# io-bus.net
KiCad netlist of a schematic drawn in Altium Designer
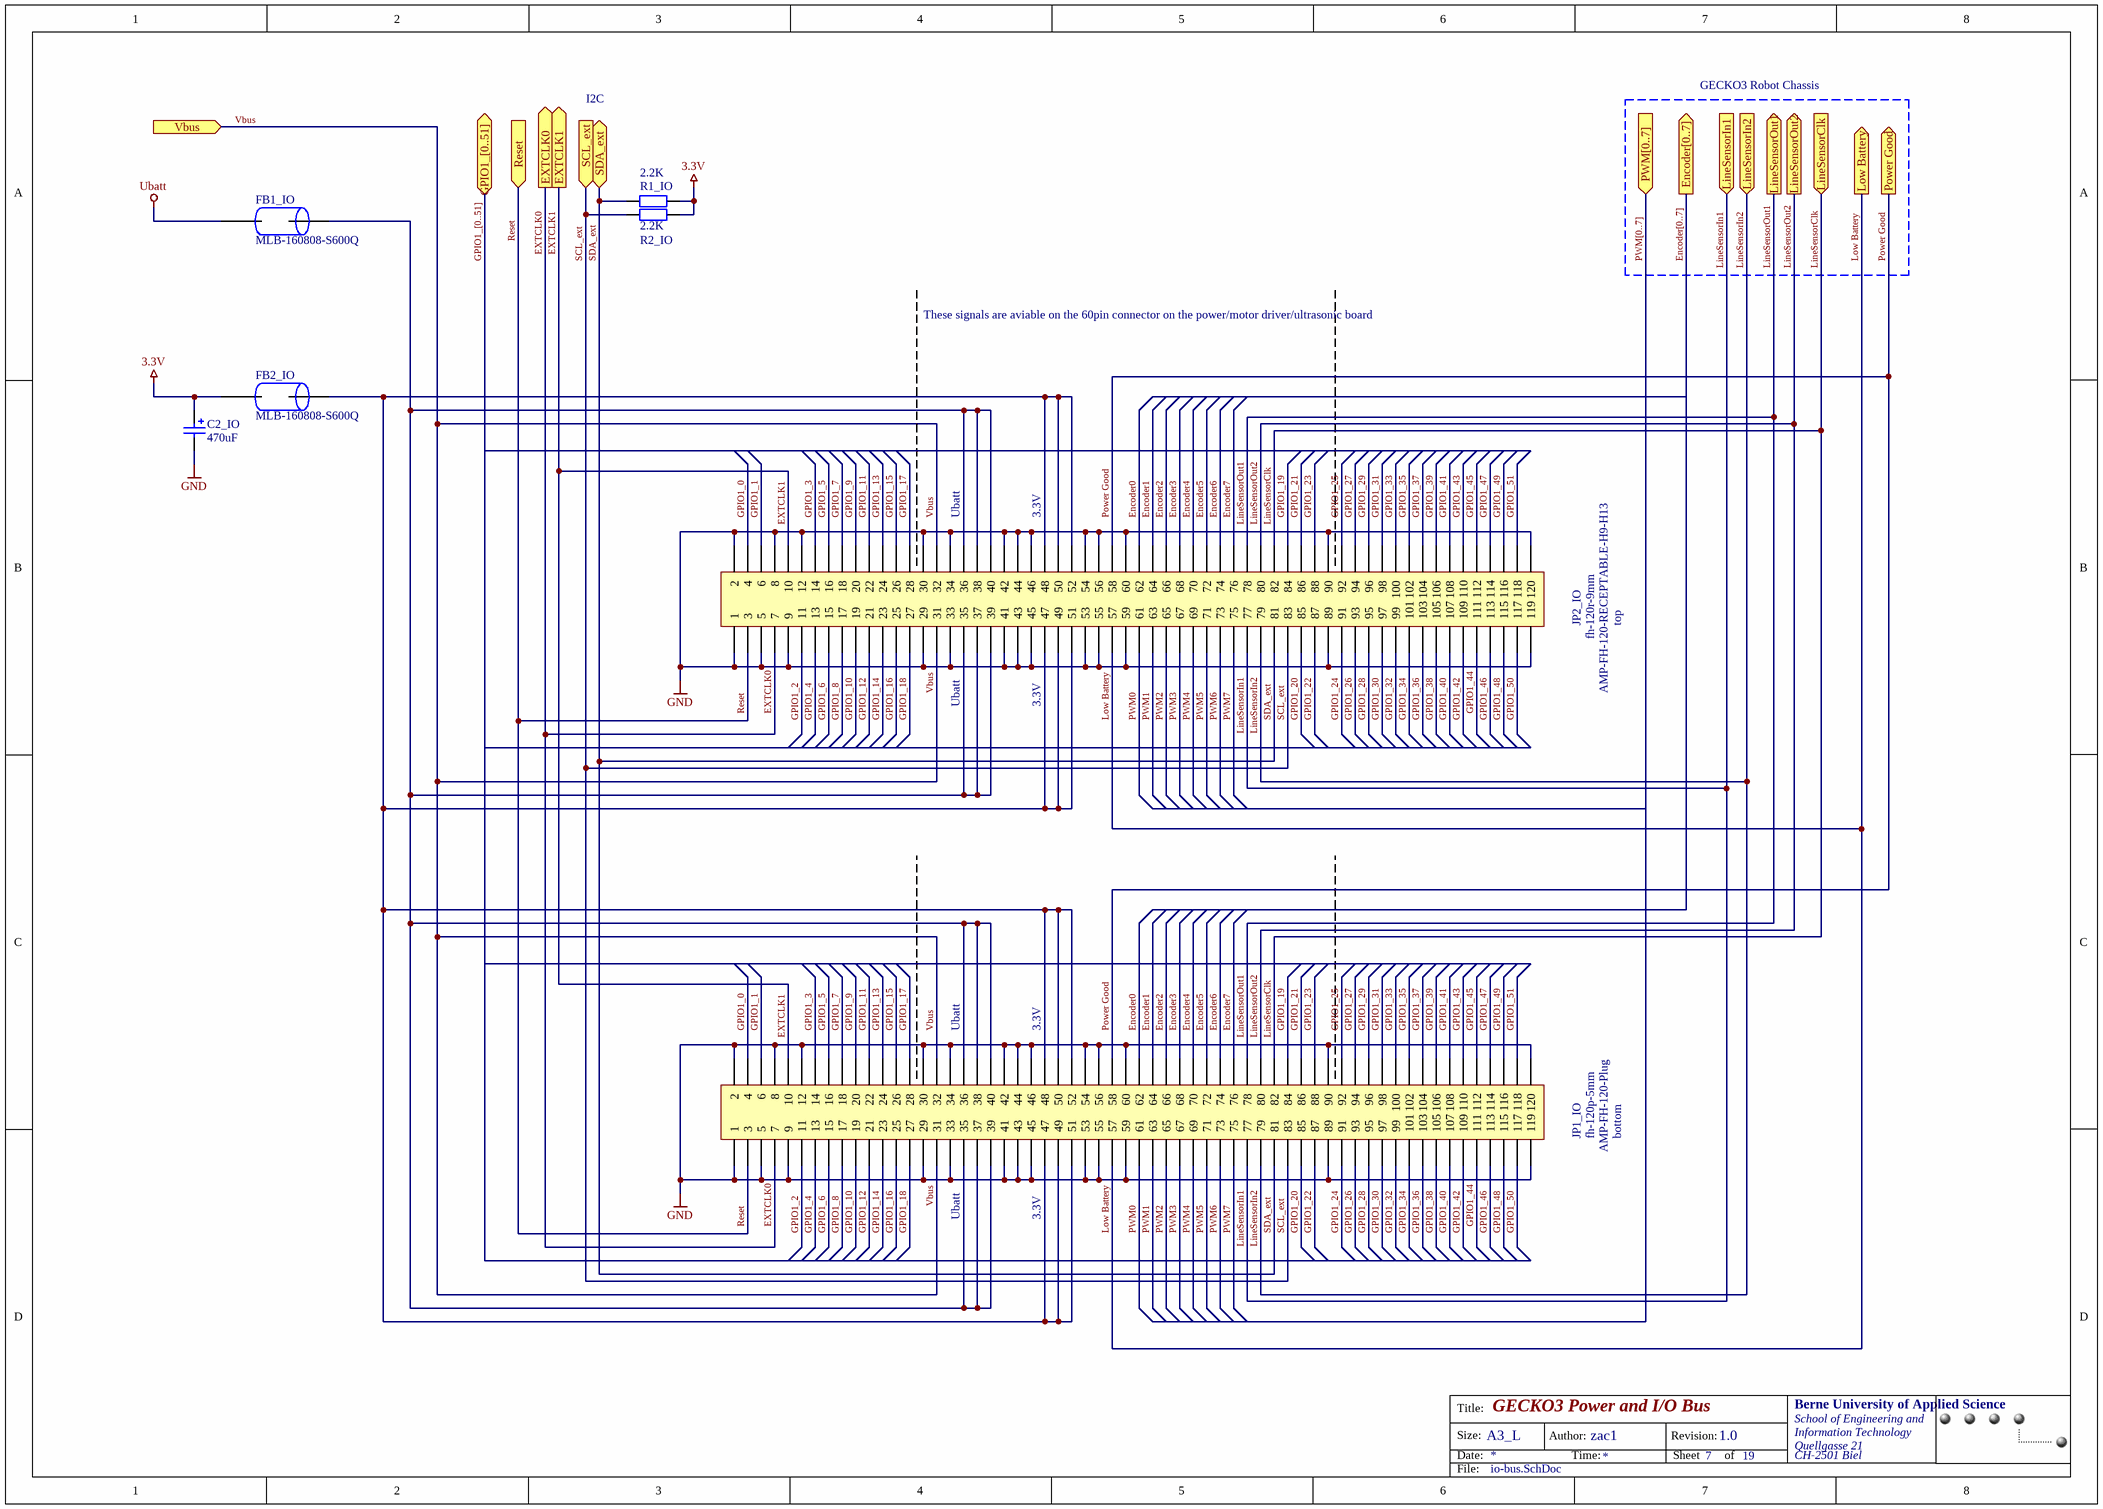
[diagram p0: io-bus.SchDoc]

(export (version "E")
  (design (tool "Eeschema 10.0.6"))
  (components
    (comp (ref "C2_IO")
      (value "470uF")
      (footprint "D")
      (description "Polarized Capacitor (Surface Mount)")
      (fields
        (field (name "MANUFACTURER") "Kemet")
        (field (name "PART NUMBER") "B45196-H2477-K509 ")
        (field (name "PUBLISHER") "Altium Limited")
      )
      (libsource (lib "Miscellaneous Devices") (part "Cap Pol3"))
    )
    (comp (ref "FB1_IO")
      (value "MLB-160808-S600Q")
      (footprint "0603")
      (fields (field (name "MANUFACTURER") "Kitagawa") (field (name "Comment") "FERRITE-BEAD"))
      (libsource (lib "gecko3-user") (part "FERRITE-BEAD"))
    )
    (comp (ref "FB2_IO")
      (value "MLB-160808-S600Q")
      (footprint "0603")
      (fields (field (name "MANUFACTURER") "Kitagawa") (field (name "Comment") "FERRITE-BEAD"))
      (libsource (lib "gecko3-user") (part "FERRITE-BEAD"))
    )
    (comp (ref "JP1_IO")
      (value "AMP-FH-120-Plug")
      (footprint "amp_FH_.8mm_120pin_plug")
      (description "AMP Free Height System, 0.8mm, 120 Pin, Plug")
      (fields
        (field (name "COMMENT_1") "bottom")
        (field (name "ALTIUM_VALUE") "fh-120p-5mm")
        (field (name "MANUFACTURER") "AMP")
        (field (name "PART NUMBER") "5177984-5")
      )
      (libsource (lib "gecko3-user") (part "AMP-FH-120-Plug"))
    )
    (comp (ref "JP2_IO")
      (value "AMP-FH-120-RECEPTABLE-H9-H13")
      (footprint "amp_FH_.8mm_120pin_r_H9_H13")
      (description "AMP Free Height System, 0.8mm, 120 Pin, 9 or 13mm Height, Receptable")
      (fields
        (field (name "ALTIUM_VALUE") "fh-120r-9mm")
        (field (name "COMMENT_1") "top")
        (field (name "MANUFACTURER") "AMP")
        (field (name "PART NUMBER") "5-5179009-5")
      )
      (libsource (lib "gecko3-user") (part "AMP-FH-120-RECEPTABLE-H9-H13"))
    )
    (comp (ref "R1_IO")
      (value "2.2K")
      (footprint "0402")
      (description "Resistor")
      (fields
        (field (name "MANUFACTURER") "PHYCOMP")
        (field (name "PART NUMBER") "232270672202")
        (field (name "PUBLISHER") "Altium Limited")
      )
      (libsource (lib "Miscellaneous Devices") (part "Res2"))
    )
    (comp (ref "R2_IO")
      (value "2.2K")
      (footprint "0402")
      (description "Resistor")
      (fields
        (field (name "MANUFACTURER") "PHYCOMP")
        (field (name "PART NUMBER") "232270672202")
        (field (name "PUBLISHER") "Altium Limited")
      )
      (libsource (lib "Miscellaneous Devices") (part "Res2"))
    )
  )
  (nets
    (net (code "1") (name "/EXTCLK0") (class "Default")
      (node (ref "JP1_IO") (pin "7") (pinfunction "7_7") (pintype "passive"))
      (node (ref "JP2_IO") (pin "7") (pinfunction "7_7") (pintype "passive"))
    )
    (net (code "2") (name "/EXTCLK1") (class "Default")
      (node (ref "JP1_IO") (pin "10") (pinfunction "10_10") (pintype "passive"))
      (node (ref "JP2_IO") (pin "10") (pinfunction "10_10") (pintype "passive"))
    )
    (net (code "3") (name "/Encoder0") (class "Default")
      (node (ref "JP1_IO") (pin "62") (pinfunction "62_62") (pintype "passive"))
      (node (ref "JP2_IO") (pin "62") (pinfunction "62_62") (pintype "passive"))
    )
    (net (code "4") (name "/Encoder1") (class "Default")
      (node (ref "JP1_IO") (pin "64") (pinfunction "64_64") (pintype "passive"))
      (node (ref "JP2_IO") (pin "64") (pinfunction "64_64") (pintype "passive"))
    )
    (net (code "5") (name "/Encoder2") (class "Default")
      (node (ref "JP1_IO") (pin "66") (pinfunction "66_66") (pintype "passive"))
      (node (ref "JP2_IO") (pin "66") (pinfunction "66_66") (pintype "passive"))
    )
    (net (code "6") (name "/Encoder3") (class "Default")
      (node (ref "JP1_IO") (pin "68") (pinfunction "68_68") (pintype "passive"))
      (node (ref "JP2_IO") (pin "68") (pinfunction "68_68") (pintype "passive"))
    )
    (net (code "7") (name "/Encoder4") (class "Default")
      (node (ref "JP1_IO") (pin "70") (pinfunction "70_70") (pintype "passive"))
      (node (ref "JP2_IO") (pin "70") (pinfunction "70_70") (pintype "passive"))
    )
    (net (code "8") (name "/Encoder5") (class "Default")
      (node (ref "JP1_IO") (pin "72") (pinfunction "72_72") (pintype "passive"))
      (node (ref "JP2_IO") (pin "72") (pinfunction "72_72") (pintype "passive"))
    )
    (net (code "9") (name "/Encoder6") (class "Default")
      (node (ref "JP1_IO") (pin "74") (pinfunction "74_74") (pintype "passive"))
      (node (ref "JP2_IO") (pin "74") (pinfunction "74_74") (pintype "passive"))
    )
    (net (code "10") (name "/Encoder7") (class "Default")
      (node (ref "JP1_IO") (pin "76") (pinfunction "76_76") (pintype "passive"))
      (node (ref "JP2_IO") (pin "76") (pinfunction "76_76") (pintype "passive"))
    )
    (net (code "12") (name "/GPIO1_0") (class "Default")
      (node (ref "JP1_IO") (pin "4") (pinfunction "4_4") (pintype "passive"))
      (node (ref "JP2_IO") (pin "4") (pinfunction "4_4") (pintype "passive"))
    )
    (net (code "13") (name "/GPIO1_1") (class "Default")
      (node (ref "JP1_IO") (pin "6") (pinfunction "6_6") (pintype "passive"))
      (node (ref "JP2_IO") (pin "6") (pinfunction "6_6") (pintype "passive"))
    )
    (net (code "14") (name "/GPIO1_2") (class "Default")
      (node (ref "JP1_IO") (pin "11") (pinfunction "11_11") (pintype "passive"))
      (node (ref "JP2_IO") (pin "11") (pinfunction "11_11") (pintype "passive"))
    )
    (net (code "15") (name "/GPIO1_3") (class "Default")
      (node (ref "JP1_IO") (pin "14") (pinfunction "14_14") (pintype "passive"))
      (node (ref "JP2_IO") (pin "14") (pinfunction "14_14") (pintype "passive"))
    )
    (net (code "16") (name "/GPIO1_4") (class "Default")
      (node (ref "JP1_IO") (pin "13") (pinfunction "13_13") (pintype "passive"))
      (node (ref "JP2_IO") (pin "13") (pinfunction "13_13") (pintype "passive"))
    )
    (net (code "17") (name "/GPIO1_5") (class "Default")
      (node (ref "JP1_IO") (pin "16") (pinfunction "16_16") (pintype "passive"))
      (node (ref "JP2_IO") (pin "16") (pinfunction "16_16") (pintype "passive"))
    )
    (net (code "18") (name "/GPIO1_6") (class "Default")
      (node (ref "JP1_IO") (pin "15") (pinfunction "15_15") (pintype "passive"))
      (node (ref "JP2_IO") (pin "15") (pinfunction "15_15") (pintype "passive"))
    )
    (net (code "19") (name "/GPIO1_7") (class "Default")
      (node (ref "JP1_IO") (pin "18") (pinfunction "18_18") (pintype "passive"))
      (node (ref "JP2_IO") (pin "18") (pinfunction "18_18") (pintype "passive"))
    )
    (net (code "20") (name "/GPIO1_8") (class "Default")
      (node (ref "JP1_IO") (pin "17") (pinfunction "17_17") (pintype "passive"))
      (node (ref "JP2_IO") (pin "17") (pinfunction "17_17") (pintype "passive"))
    )
    (net (code "21") (name "/GPIO1_9") (class "Default")
      (node (ref "JP1_IO") (pin "20") (pinfunction "20_20") (pintype "passive"))
      (node (ref "JP2_IO") (pin "20") (pinfunction "20_20") (pintype "passive"))
    )
    (net (code "22") (name "/GPIO1_10") (class "Default")
      (node (ref "JP1_IO") (pin "19") (pinfunction "19_19") (pintype "passive"))
      (node (ref "JP2_IO") (pin "19") (pinfunction "19_19") (pintype "passive"))
    )
    (net (code "23") (name "/GPIO1_11") (class "Default")
      (node (ref "JP1_IO") (pin "22") (pinfunction "22_22") (pintype "passive"))
      (node (ref "JP2_IO") (pin "22") (pinfunction "22_22") (pintype "passive"))
    )
    (net (code "24") (name "/GPIO1_12") (class "Default")
      (node (ref "JP1_IO") (pin "21") (pinfunction "21_21") (pintype "passive"))
      (node (ref "JP2_IO") (pin "21") (pinfunction "21_21") (pintype "passive"))
    )
    (net (code "25") (name "/GPIO1_13") (class "Default")
      (node (ref "JP1_IO") (pin "24") (pinfunction "24_24") (pintype "passive"))
      (node (ref "JP2_IO") (pin "24") (pinfunction "24_24") (pintype "passive"))
    )
    (net (code "26") (name "/GPIO1_14") (class "Default")
      (node (ref "JP1_IO") (pin "23") (pinfunction "23_23") (pintype "passive"))
      (node (ref "JP2_IO") (pin "23") (pinfunction "23_23") (pintype "passive"))
    )
    (net (code "27") (name "/GPIO1_15") (class "Default")
      (node (ref "JP1_IO") (pin "26") (pinfunction "26_26") (pintype "passive"))
      (node (ref "JP2_IO") (pin "26") (pinfunction "26_26") (pintype "passive"))
    )
    (net (code "28") (name "/GPIO1_16") (class "Default")
      (node (ref "JP1_IO") (pin "25") (pinfunction "25_25") (pintype "passive"))
      (node (ref "JP2_IO") (pin "25") (pinfunction "25_25") (pintype "passive"))
    )
    (net (code "29") (name "/GPIO1_17") (class "Default")
      (node (ref "JP1_IO") (pin "28") (pinfunction "28_28") (pintype "passive"))
      (node (ref "JP2_IO") (pin "28") (pinfunction "28_28") (pintype "passive"))
    )
    (net (code "30") (name "/GPIO1_18") (class "Default")
      (node (ref "JP1_IO") (pin "27") (pinfunction "27_27") (pintype "passive"))
      (node (ref "JP2_IO") (pin "27") (pinfunction "27_27") (pintype "passive"))
    )
    (net (code "31") (name "/GPIO1_19") (class "Default")
      (node (ref "JP1_IO") (pin "84") (pinfunction "84_84") (pintype "passive"))
      (node (ref "JP2_IO") (pin "84") (pinfunction "84_84") (pintype "passive"))
    )
    (net (code "32") (name "/GPIO1_20") (class "Default")
      (node (ref "JP1_IO") (pin "85") (pinfunction "85_85") (pintype "passive"))
      (node (ref "JP2_IO") (pin "85") (pinfunction "85_85") (pintype "passive"))
    )
    (net (code "33") (name "/GPIO1_21") (class "Default")
      (node (ref "JP1_IO") (pin "86") (pinfunction "86_86") (pintype "passive"))
      (node (ref "JP2_IO") (pin "86") (pinfunction "86_86") (pintype "passive"))
    )
    (net (code "34") (name "/GPIO1_22") (class "Default")
      (node (ref "JP1_IO") (pin "87") (pinfunction "87_87") (pintype "passive"))
      (node (ref "JP2_IO") (pin "87") (pinfunction "87_87") (pintype "passive"))
    )
    (net (code "35") (name "/GPIO1_23") (class "Default")
      (node (ref "JP1_IO") (pin "88") (pinfunction "88_88") (pintype "passive"))
      (node (ref "JP2_IO") (pin "88") (pinfunction "88_88") (pintype "passive"))
    )
    (net (code "36") (name "/GPIO1_24") (class "Default")
      (node (ref "JP1_IO") (pin "91") (pinfunction "91_91") (pintype "passive"))
      (node (ref "JP2_IO") (pin "91") (pinfunction "91_91") (pintype "passive"))
    )
    (net (code "37") (name "/GPIO1_25") (class "Default")
      (node (ref "JP1_IO") (pin "92") (pinfunction "92_92") (pintype "passive"))
      (node (ref "JP2_IO") (pin "92") (pinfunction "92_92") (pintype "passive"))
    )
    (net (code "38") (name "/GPIO1_26") (class "Default")
      (node (ref "JP1_IO") (pin "93") (pinfunction "93_93") (pintype "passive"))
      (node (ref "JP2_IO") (pin "93") (pinfunction "93_93") (pintype "passive"))
    )
    (net (code "39") (name "/GPIO1_27") (class "Default")
      (node (ref "JP1_IO") (pin "94") (pinfunction "94_94") (pintype "passive"))
      (node (ref "JP2_IO") (pin "94") (pinfunction "94_94") (pintype "passive"))
    )
    (net (code "40") (name "/GPIO1_28") (class "Default")
      (node (ref "JP1_IO") (pin "95") (pinfunction "95_95") (pintype "passive"))
      (node (ref "JP2_IO") (pin "95") (pinfunction "95_95") (pintype "passive"))
    )
    (net (code "41") (name "/GPIO1_29") (class "Default")
      (node (ref "JP1_IO") (pin "96") (pinfunction "96_96") (pintype "passive"))
      (node (ref "JP2_IO") (pin "96") (pinfunction "96_96") (pintype "passive"))
    )
    (net (code "42") (name "/GPIO1_30") (class "Default")
      (node (ref "JP1_IO") (pin "97") (pinfunction "97_97") (pintype "passive"))
      (node (ref "JP2_IO") (pin "97") (pinfunction "97_97") (pintype "passive"))
    )
    (net (code "43") (name "/GPIO1_31") (class "Default")
      (node (ref "JP1_IO") (pin "98") (pinfunction "98_98") (pintype "passive"))
      (node (ref "JP2_IO") (pin "98") (pinfunction "98_98") (pintype "passive"))
    )
    (net (code "44") (name "/GPIO1_32") (class "Default")
      (node (ref "JP1_IO") (pin "99") (pinfunction "99_99") (pintype "passive"))
      (node (ref "JP2_IO") (pin "99") (pinfunction "99_99") (pintype "passive"))
    )
    (net (code "45") (name "/GPIO1_33") (class "Default")
      (node (ref "JP1_IO") (pin "100") (pinfunction "100_100") (pintype "passive"))
      (node (ref "JP2_IO") (pin "100") (pinfunction "100_100") (pintype "passive"))
    )
    (net (code "46") (name "/GPIO1_34") (class "Default")
      (node (ref "JP1_IO") (pin "101") (pinfunction "101_101") (pintype "passive"))
      (node (ref "JP2_IO") (pin "101") (pinfunction "101_101") (pintype "passive"))
    )
    (net (code "47") (name "/GPIO1_35") (class "Default")
      (node (ref "JP1_IO") (pin "102") (pinfunction "102_102") (pintype "passive"))
      (node (ref "JP2_IO") (pin "102") (pinfunction "102_102") (pintype "passive"))
    )
    (net (code "48") (name "/GPIO1_36") (class "Default")
      (node (ref "JP1_IO") (pin "103") (pinfunction "103_103") (pintype "passive"))
      (node (ref "JP2_IO") (pin "103") (pinfunction "103_103") (pintype "passive"))
    )
    (net (code "49") (name "/GPIO1_37") (class "Default")
      (node (ref "JP1_IO") (pin "104") (pinfunction "104_104") (pintype "passive"))
      (node (ref "JP2_IO") (pin "104") (pinfunction "104_104") (pintype "passive"))
    )
    (net (code "50") (name "/GPIO1_38") (class "Default")
      (node (ref "JP1_IO") (pin "105") (pinfunction "105_105") (pintype "passive"))
      (node (ref "JP2_IO") (pin "105") (pinfunction "105_105") (pintype "passive"))
    )
    (net (code "51") (name "/GPIO1_39") (class "Default")
      (node (ref "JP1_IO") (pin "106") (pinfunction "106_106") (pintype "passive"))
      (node (ref "JP2_IO") (pin "106") (pinfunction "106_106") (pintype "passive"))
    )
    (net (code "52") (name "/GPIO1_40") (class "Default")
      (node (ref "JP1_IO") (pin "107") (pinfunction "107_107") (pintype "passive"))
      (node (ref "JP2_IO") (pin "107") (pinfunction "107_107") (pintype "passive"))
    )
    (net (code "53") (name "/GPIO1_41") (class "Default")
      (node (ref "JP1_IO") (pin "108") (pinfunction "108_108") (pintype "passive"))
      (node (ref "JP2_IO") (pin "108") (pinfunction "108_108") (pintype "passive"))
    )
    (net (code "54") (name "/GPIO1_42") (class "Default")
      (node (ref "JP1_IO") (pin "109") (pinfunction "109_109") (pintype "passive"))
      (node (ref "JP2_IO") (pin "109") (pinfunction "109_109") (pintype "passive"))
    )
    (net (code "55") (name "/GPIO1_43") (class "Default")
      (node (ref "JP1_IO") (pin "110") (pinfunction "110_110") (pintype "passive"))
      (node (ref "JP2_IO") (pin "110") (pinfunction "110_110") (pintype "passive"))
    )
    (net (code "56") (name "/GPIO1_44") (class "Default")
      (node (ref "JP1_IO") (pin "111") (pinfunction "111_111") (pintype "passive"))
      (node (ref "JP2_IO") (pin "111") (pinfunction "111_111") (pintype "passive"))
    )
    (net (code "57") (name "/GPIO1_45") (class "Default")
      (node (ref "JP1_IO") (pin "112") (pinfunction "112_112") (pintype "passive"))
      (node (ref "JP2_IO") (pin "112") (pinfunction "112_112") (pintype "passive"))
    )
    (net (code "58") (name "/GPIO1_46") (class "Default")
      (node (ref "JP1_IO") (pin "113") (pinfunction "113_113") (pintype "passive"))
      (node (ref "JP2_IO") (pin "113") (pinfunction "113_113") (pintype "passive"))
    )
    (net (code "59") (name "/GPIO1_47") (class "Default")
      (node (ref "JP1_IO") (pin "114") (pinfunction "114_114") (pintype "passive"))
      (node (ref "JP2_IO") (pin "114") (pinfunction "114_114") (pintype "passive"))
    )
    (net (code "60") (name "/GPIO1_48") (class "Default")
      (node (ref "JP1_IO") (pin "115") (pinfunction "115_115") (pintype "passive"))
      (node (ref "JP2_IO") (pin "115") (pinfunction "115_115") (pintype "passive"))
    )
    (net (code "61") (name "/GPIO1_49") (class "Default")
      (node (ref "JP1_IO") (pin "116") (pinfunction "116_116") (pintype "passive"))
      (node (ref "JP2_IO") (pin "116") (pinfunction "116_116") (pintype "passive"))
    )
    (net (code "62") (name "/GPIO1_50") (class "Default")
      (node (ref "JP1_IO") (pin "117") (pinfunction "117_117") (pintype "passive"))
      (node (ref "JP2_IO") (pin "117") (pinfunction "117_117") (pintype "passive"))
    )
    (net (code "63") (name "/GPIO1_51") (class "Default")
      (node (ref "JP1_IO") (pin "118") (pinfunction "118_118") (pintype "passive"))
      (node (ref "JP2_IO") (pin "118") (pinfunction "118_118") (pintype "passive"))
    )
    (net (code "65") (name "/LineSensorClk") (class "Default")
      (node (ref "JP1_IO") (pin "82") (pinfunction "82_82") (pintype "passive"))
      (node (ref "JP2_IO") (pin "82") (pinfunction "82_82") (pintype "passive"))
    )
    (net (code "66") (name "/LineSensorIn1") (class "Default")
      (node (ref "JP1_IO") (pin "77") (pinfunction "77_77") (pintype "passive"))
      (node (ref "JP2_IO") (pin "77") (pinfunction "77_77") (pintype "passive"))
    )
    (net (code "67") (name "/LineSensorIn2") (class "Default")
      (node (ref "JP1_IO") (pin "79") (pinfunction "79_79") (pintype "passive"))
      (node (ref "JP2_IO") (pin "79") (pinfunction "79_79") (pintype "passive"))
    )
    (net (code "68") (name "/LineSensorOut1") (class "Default")
      (node (ref "JP1_IO") (pin "78") (pinfunction "78_78") (pintype "passive"))
      (node (ref "JP2_IO") (pin "78") (pinfunction "78_78") (pintype "passive"))
    )
    (net (code "69") (name "/LineSensorOut2") (class "Default")
      (node (ref "JP1_IO") (pin "80") (pinfunction "80_80") (pintype "passive"))
      (node (ref "JP2_IO") (pin "80") (pinfunction "80_80") (pintype "passive"))
    )
    (net (code "70") (name "/Low Battery") (class "Default")
      (node (ref "JP1_IO") (pin "57") (pinfunction "57_57") (pintype "passive"))
      (node (ref "JP2_IO") (pin "57") (pinfunction "57_57") (pintype "passive"))
    )
    (net (code "71") (name "/PWM0") (class "Default")
      (node (ref "JP1_IO") (pin "61") (pinfunction "61_61") (pintype "passive"))
      (node (ref "JP2_IO") (pin "61") (pinfunction "61_61") (pintype "passive"))
    )
    (net (code "72") (name "/PWM1") (class "Default")
      (node (ref "JP1_IO") (pin "63") (pinfunction "63_63") (pintype "passive"))
      (node (ref "JP2_IO") (pin "63") (pinfunction "63_63") (pintype "passive"))
    )
    (net (code "73") (name "/PWM2") (class "Default")
      (node (ref "JP1_IO") (pin "65") (pinfunction "65_65") (pintype "passive"))
      (node (ref "JP2_IO") (pin "65") (pinfunction "65_65") (pintype "passive"))
    )
    (net (code "74") (name "/PWM3") (class "Default")
      (node (ref "JP1_IO") (pin "67") (pinfunction "67_67") (pintype "passive"))
      (node (ref "JP2_IO") (pin "67") (pinfunction "67_67") (pintype "passive"))
    )
    (net (code "75") (name "/PWM4") (class "Default")
      (node (ref "JP1_IO") (pin "69") (pinfunction "69_69") (pintype "passive"))
      (node (ref "JP2_IO") (pin "69") (pinfunction "69_69") (pintype "passive"))
    )
    (net (code "76") (name "/PWM5") (class "Default")
      (node (ref "JP1_IO") (pin "71") (pinfunction "71_71") (pintype "passive"))
      (node (ref "JP2_IO") (pin "71") (pinfunction "71_71") (pintype "passive"))
    )
    (net (code "77") (name "/PWM6") (class "Default")
      (node (ref "JP1_IO") (pin "73") (pinfunction "73_73") (pintype "passive"))
      (node (ref "JP2_IO") (pin "73") (pinfunction "73_73") (pintype "passive"))
    )
    (net (code "78") (name "/PWM7") (class "Default")
      (node (ref "JP1_IO") (pin "75") (pinfunction "75_75") (pintype "passive"))
      (node (ref "JP2_IO") (pin "75") (pinfunction "75_75") (pintype "passive"))
    )
    (net (code "80") (name "/Power Good") (class "Default")
      (node (ref "JP1_IO") (pin "58") (pinfunction "58_58") (pintype "passive"))
      (node (ref "JP2_IO") (pin "58") (pinfunction "58_58") (pintype "passive"))
    )
    (net (code "81") (name "/Reset") (class "Default")
      (node (ref "JP1_IO") (pin "3") (pinfunction "3_3") (pintype "passive"))
      (node (ref "JP2_IO") (pin "3") (pinfunction "3_3") (pintype "passive"))
    )
    (net (code "82") (name "/SCL_ext") (class "Default")
      (node (ref "JP1_IO") (pin "83") (pinfunction "83_83") (pintype "passive"))
      (node (ref "JP2_IO") (pin "83") (pinfunction "83_83") (pintype "passive"))
      (node (ref "R2_IO") (pin "1") (pinfunction "1_1") (pintype "passive"))
    )
    (net (code "83") (name "/SDA_ext") (class "Default")
      (node (ref "JP1_IO") (pin "81") (pinfunction "81_81") (pintype "passive"))
      (node (ref "JP2_IO") (pin "81") (pinfunction "81_81") (pintype "passive"))
      (node (ref "R1_IO") (pin "1") (pinfunction "1_1") (pintype "passive"))
    )
    (net (code "84") (name "/Vbus") (class "Default")
      (node (ref "JP1_IO") (pin "31") (pinfunction "31_31") (pintype "passive"))
      (node (ref "JP1_IO") (pin "32") (pinfunction "32_32") (pintype "passive"))
      (node (ref "JP2_IO") (pin "31") (pinfunction "31_31") (pintype "passive"))
      (node (ref "JP2_IO") (pin "32") (pinfunction "32_32") (pintype "passive"))
    )
    (net (code "85") (name "3.3V") (class "Default")
      (node (ref "C2_IO") (pin "1") (pinfunction "1_1") (pintype "passive"))
      (node (ref "FB2_IO") (pin "1") (pinfunction "1_1") (pintype "passive"))
      (node (ref "R1_IO") (pin "2") (pinfunction "2_2") (pintype "passive"))
      (node (ref "R2_IO") (pin "2") (pinfunction "2_2") (pintype "passive"))
    )
    (net (code "86") (name "GND") (class "Default")
      (node (ref "C2_IO") (pin "2") (pinfunction "2_2") (pintype "passive"))
      (node (ref "JP1_IO") (pin "1") (pinfunction "1_1") (pintype "passive"))
      (node (ref "JP1_IO") (pin "119") (pinfunction "119_119") (pintype "passive"))
      (node (ref "JP1_IO") (pin "12") (pinfunction "12_12") (pintype "passive"))
      (node (ref "JP1_IO") (pin "120") (pinfunction "120_120") (pintype "passive"))
      (node (ref "JP1_IO") (pin "2") (pinfunction "2_2") (pintype "passive"))
      (node (ref "JP1_IO") (pin "29") (pinfunction "29_29") (pintype "passive"))
      (node (ref "JP1_IO") (pin "30") (pinfunction "30_30") (pintype "passive"))
      (node (ref "JP1_IO") (pin "33") (pinfunction "33_33") (pintype "passive"))
      (node (ref "JP1_IO") (pin "34") (pinfunction "34_34") (pintype "passive"))
      (node (ref "JP1_IO") (pin "41") (pinfunction "41_41") (pintype "passive"))
      (node (ref "JP1_IO") (pin "42") (pinfunction "42_42") (pintype "passive"))
      (node (ref "JP1_IO") (pin "43") (pinfunction "43_43") (pintype "passive"))
      (node (ref "JP1_IO") (pin "44") (pinfunction "44_44") (pintype "passive"))
      (node (ref "JP1_IO") (pin "45") (pinfunction "45_45") (pintype "passive"))
      (node (ref "JP1_IO") (pin "46") (pinfunction "46_46") (pintype "passive"))
      (node (ref "JP1_IO") (pin "5") (pinfunction "5_5") (pintype "passive"))
      (node (ref "JP1_IO") (pin "53") (pinfunction "53_53") (pintype "passive"))
      (node (ref "JP1_IO") (pin "54") (pinfunction "54_54") (pintype "passive"))
      (node (ref "JP1_IO") (pin "55") (pinfunction "55_55") (pintype "passive"))
      (node (ref "JP1_IO") (pin "56") (pinfunction "56_56") (pintype "passive"))
      (node (ref "JP1_IO") (pin "59") (pinfunction "59_59") (pintype "passive"))
      (node (ref "JP1_IO") (pin "60") (pinfunction "60_60") (pintype "passive"))
      (node (ref "JP1_IO") (pin "8") (pinfunction "8_8") (pintype "passive"))
      (node (ref "JP1_IO") (pin "89") (pinfunction "89_89") (pintype "passive"))
      (node (ref "JP1_IO") (pin "9") (pinfunction "9_9") (pintype "passive"))
      (node (ref "JP1_IO") (pin "90") (pinfunction "90_90") (pintype "passive"))
      (node (ref "JP2_IO") (pin "1") (pinfunction "1_1") (pintype "passive"))
      (node (ref "JP2_IO") (pin "119") (pinfunction "119_119") (pintype "passive"))
      (node (ref "JP2_IO") (pin "12") (pinfunction "12_12") (pintype "passive"))
      (node (ref "JP2_IO") (pin "120") (pinfunction "120_120") (pintype "passive"))
      (node (ref "JP2_IO") (pin "2") (pinfunction "2_2") (pintype "passive"))
      (node (ref "JP2_IO") (pin "29") (pinfunction "29_29") (pintype "passive"))
      (node (ref "JP2_IO") (pin "30") (pinfunction "30_30") (pintype "passive"))
      (node (ref "JP2_IO") (pin "33") (pinfunction "33_33") (pintype "passive"))
      (node (ref "JP2_IO") (pin "34") (pinfunction "34_34") (pintype "passive"))
      (node (ref "JP2_IO") (pin "41") (pinfunction "41_41") (pintype "passive"))
      (node (ref "JP2_IO") (pin "42") (pinfunction "42_42") (pintype "passive"))
      (node (ref "JP2_IO") (pin "43") (pinfunction "43_43") (pintype "passive"))
      (node (ref "JP2_IO") (pin "44") (pinfunction "44_44") (pintype "passive"))
      (node (ref "JP2_IO") (pin "45") (pinfunction "45_45") (pintype "passive"))
      (node (ref "JP2_IO") (pin "46") (pinfunction "46_46") (pintype "passive"))
      (node (ref "JP2_IO") (pin "5") (pinfunction "5_5") (pintype "passive"))
      (node (ref "JP2_IO") (pin "53") (pinfunction "53_53") (pintype "passive"))
      (node (ref "JP2_IO") (pin "54") (pinfunction "54_54") (pintype "passive"))
      (node (ref "JP2_IO") (pin "55") (pinfunction "55_55") (pintype "passive"))
      (node (ref "JP2_IO") (pin "56") (pinfunction "56_56") (pintype "passive"))
      (node (ref "JP2_IO") (pin "59") (pinfunction "59_59") (pintype "passive"))
      (node (ref "JP2_IO") (pin "60") (pinfunction "60_60") (pintype "passive"))
      (node (ref "JP2_IO") (pin "8") (pinfunction "8_8") (pintype "passive"))
      (node (ref "JP2_IO") (pin "89") (pinfunction "89_89") (pintype "passive"))
      (node (ref "JP2_IO") (pin "9") (pinfunction "9_9") (pintype "passive"))
      (node (ref "JP2_IO") (pin "90") (pinfunction "90_90") (pintype "passive"))
    )
    (net (code "87") (name "Net-(FB1_IO-Pad2)") (class "Default")
      (node (ref "FB1_IO") (pin "2") (pinfunction "2_2") (pintype "passive"))
      (node (ref "JP1_IO") (pin "35") (pinfunction "35_35") (pintype "passive"))
      (node (ref "JP1_IO") (pin "36") (pinfunction "36_36") (pintype "passive"))
      (node (ref "JP1_IO") (pin "37") (pinfunction "37_37") (pintype "passive"))
      (node (ref "JP1_IO") (pin "38") (pinfunction "38_38") (pintype "passive"))
      (node (ref "JP1_IO") (pin "39") (pinfunction "39_39") (pintype "passive"))
      (node (ref "JP1_IO") (pin "40") (pinfunction "40_40") (pintype "passive"))
      (node (ref "JP2_IO") (pin "35") (pinfunction "35_35") (pintype "passive"))
      (node (ref "JP2_IO") (pin "36") (pinfunction "36_36") (pintype "passive"))
      (node (ref "JP2_IO") (pin "37") (pinfunction "37_37") (pintype "passive"))
      (node (ref "JP2_IO") (pin "38") (pinfunction "38_38") (pintype "passive"))
      (node (ref "JP2_IO") (pin "39") (pinfunction "39_39") (pintype "passive"))
      (node (ref "JP2_IO") (pin "40") (pinfunction "40_40") (pintype "passive"))
    )
    (net (code "88") (name "Net-(FB2_IO-Pad2)") (class "Default")
      (node (ref "FB2_IO") (pin "2") (pinfunction "2_2") (pintype "passive"))
      (node (ref "JP1_IO") (pin "47") (pinfunction "47_47") (pintype "passive"))
      (node (ref "JP1_IO") (pin "48") (pinfunction "48_48") (pintype "passive"))
      (node (ref "JP1_IO") (pin "49") (pinfunction "49_49") (pintype "passive"))
      (node (ref "JP1_IO") (pin "50") (pinfunction "50_50") (pintype "passive"))
      (node (ref "JP1_IO") (pin "51") (pinfunction "51_51") (pintype "passive"))
      (node (ref "JP1_IO") (pin "52") (pinfunction "52_52") (pintype "passive"))
      (node (ref "JP2_IO") (pin "47") (pinfunction "47_47") (pintype "passive"))
      (node (ref "JP2_IO") (pin "48") (pinfunction "48_48") (pintype "passive"))
      (node (ref "JP2_IO") (pin "49") (pinfunction "49_49") (pintype "passive"))
      (node (ref "JP2_IO") (pin "50") (pinfunction "50_50") (pintype "passive"))
      (node (ref "JP2_IO") (pin "51") (pinfunction "51_51") (pintype "passive"))
      (node (ref "JP2_IO") (pin "52") (pinfunction "52_52") (pintype "passive"))
    )
    (net (code "89") (name "Ubatt") (class "Default")
      (node (ref "FB1_IO") (pin "1") (pinfunction "1_1") (pintype "passive"))
    )
  )
)
